# untitled.net
KiCad netlist of a schematic drawn in EAGLE
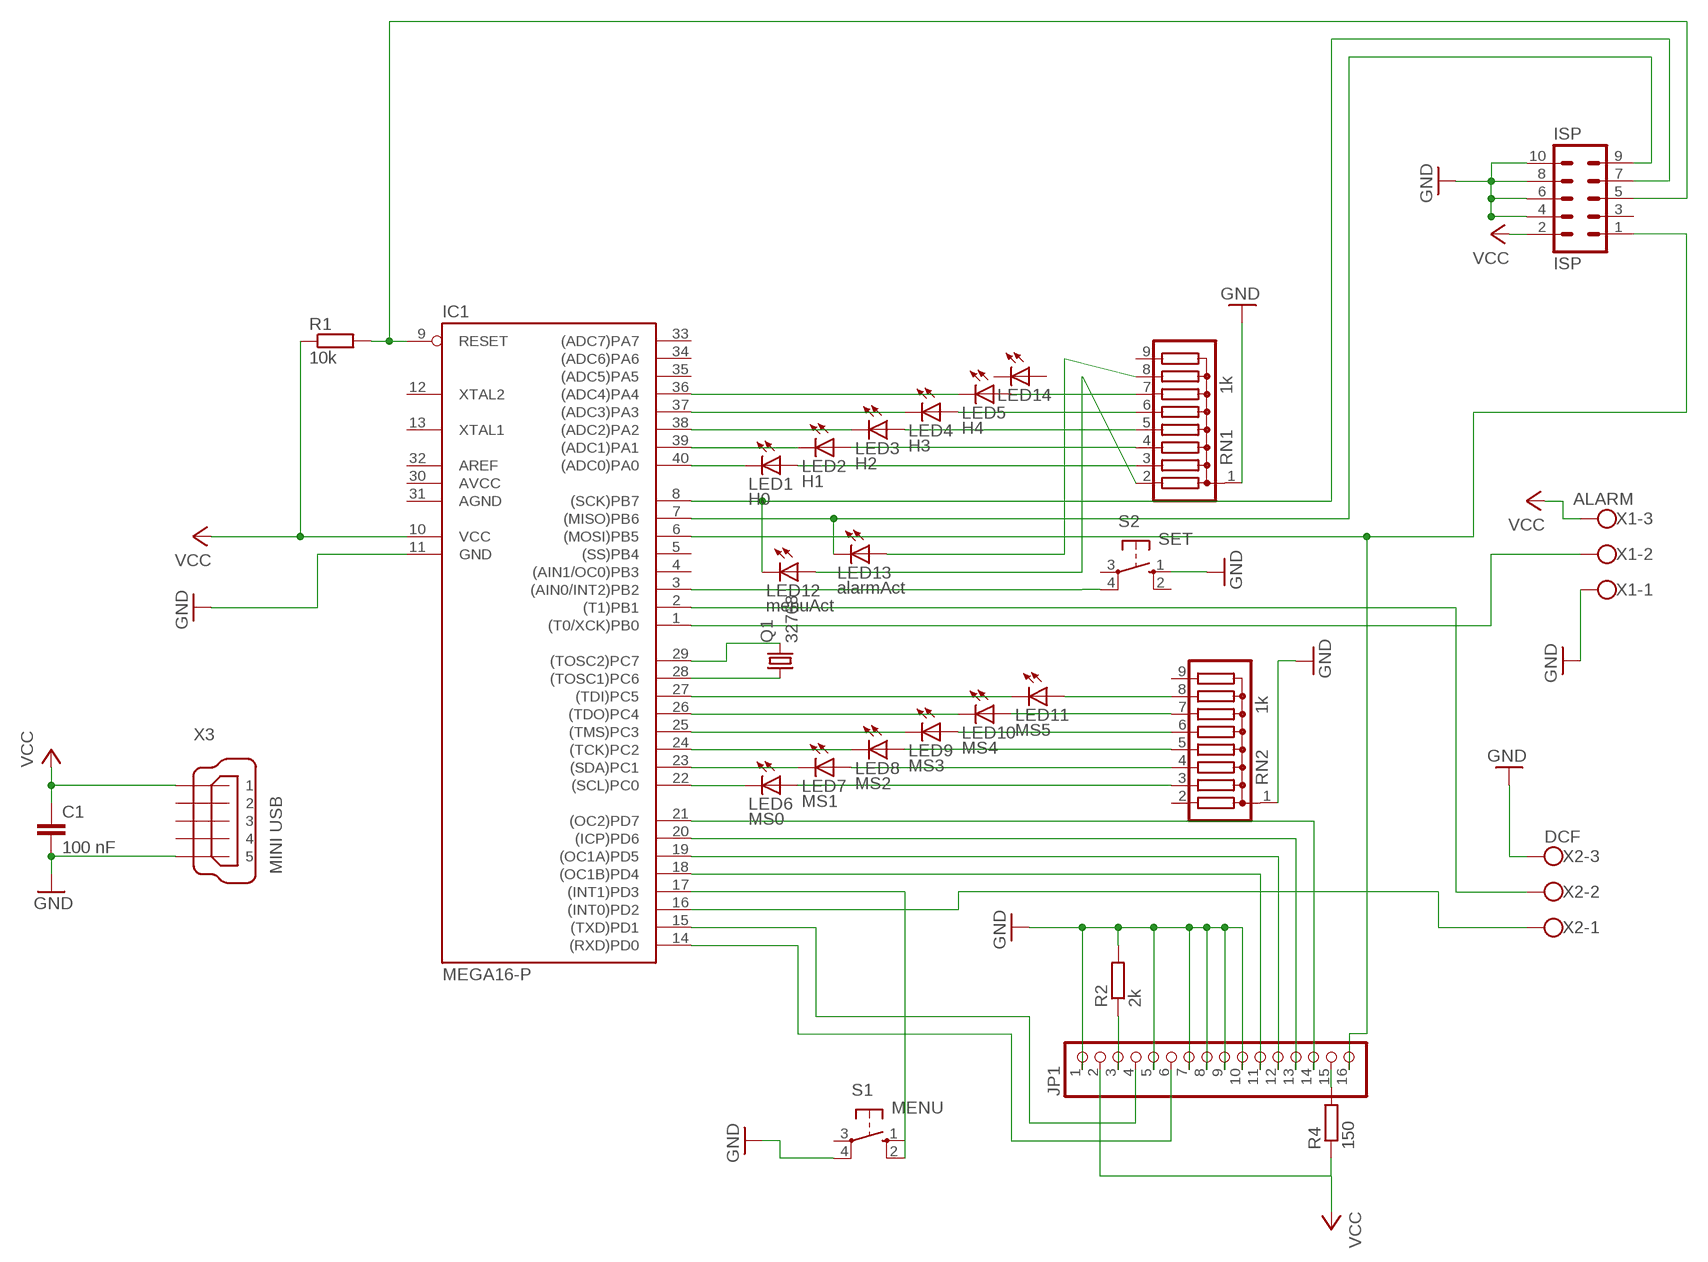
[diagram p0: schematic, sheet 1]

(export (version "E")
  (design (tool "Eeschema 10.0.6"))
  (components
    (comp (ref "C1")
      (value "100 nF")
      (footprint "eagle-import:C050-025X075")
      (libsource (lib "eagle-import") (part "C-EU050-025X075"))
    )
    (comp (ref "IC1")
      (value "MEGA16-P")
      (footprint "eagle-import:DIL40")
      (libsource (lib "eagle-import") (part "MEGA16-P"))
    )
    (comp (ref "ISP")
      (value "ISP")
      (footprint "eagle-import:ML10")
      (libsource (lib "eagle-import") (part "ML10"))
    )
    (comp (ref "JP1")
      (value "PINHD-1X16")
      (footprint "eagle-import:1X16")
      (libsource (lib "eagle-import") (part "PINHD-1X16"))
    )
    (comp (ref "LED1")
      (value "H0")
      (footprint "eagle-import:LED3MM")
      (libsource (lib "eagle-import") (part "LED3MM"))
    )
    (comp (ref "LED2")
      (value "H1")
      (footprint "eagle-import:LED3MM")
      (libsource (lib "eagle-import") (part "LED3MM"))
    )
    (comp (ref "LED3")
      (value "H2")
      (footprint "eagle-import:LED3MM")
      (libsource (lib "eagle-import") (part "LED3MM"))
    )
    (comp (ref "LED4")
      (value "H3")
      (footprint "eagle-import:LED3MM")
      (libsource (lib "eagle-import") (part "LED3MM"))
    )
    (comp (ref "LED5")
      (value "H4")
      (footprint "eagle-import:LED3MM")
      (libsource (lib "eagle-import") (part "LED3MM"))
    )
    (comp (ref "LED6")
      (value "MS0")
      (footprint "eagle-import:LED3MM")
      (libsource (lib "eagle-import") (part "LED3MM"))
    )
    (comp (ref "LED7")
      (value "MS1")
      (footprint "eagle-import:LED3MM")
      (libsource (lib "eagle-import") (part "LED3MM"))
    )
    (comp (ref "LED8")
      (value "MS2")
      (footprint "eagle-import:LED3MM")
      (libsource (lib "eagle-import") (part "LED3MM"))
    )
    (comp (ref "LED9")
      (value "MS3")
      (footprint "eagle-import:LED3MM")
      (libsource (lib "eagle-import") (part "LED3MM"))
    )
    (comp (ref "LED10")
      (value "MS4")
      (footprint "eagle-import:LED3MM")
      (libsource (lib "eagle-import") (part "LED3MM"))
    )
    (comp (ref "LED11")
      (value "MS5")
      (footprint "eagle-import:LED3MM")
      (libsource (lib "eagle-import") (part "LED3MM"))
    )
    (comp (ref "LED12")
      (value "menuAct")
      (footprint "eagle-import:LED3MM")
      (libsource (lib "eagle-import") (part "LED3MM"))
    )
    (comp (ref "LED13")
      (value "alarmAct")
      (footprint "eagle-import:LED3MM")
      (libsource (lib "eagle-import") (part "LED3MM"))
    )
    (comp (ref "LED14")
      (value "LED3MM")
      (footprint "eagle-import:LED3MM")
      (libsource (lib "eagle-import") (part "LED3MM"))
    )
    (comp (ref "Q1")
      (value "32768")
      (footprint "eagle-import:TC26V")
      (libsource (lib "eagle-import") (part "CRYSTALTC26V"))
    )
    (comp (ref "R1")
      (value "10k")
      (footprint "eagle-import:0207_10")
      (libsource (lib "eagle-import") (part "R-EU_0207/10"))
    )
    (comp (ref "R2")
      (value "2k")
      (footprint "eagle-import:0207_10")
      (libsource (lib "eagle-import") (part "R-EU_0207/10"))
    )
    (comp (ref "R4")
      (value "150")
      (footprint "eagle-import:0204_7")
      (libsource (lib "eagle-import") (part "R-EU_0204/7"))
    )
    (comp (ref "RN1")
      (value "1k")
      (footprint "eagle-import:SIL9")
      (libsource (lib "eagle-import") (part "G08R"))
    )
    (comp (ref "RN2")
      (value "1k")
      (footprint "eagle-import:SIL9")
      (libsource (lib "eagle-import") (part "G08R"))
    )
    (comp (ref "S1")
      (value "MENU")
      (footprint "eagle-import:B3F-10XX")
      (libsource (lib "eagle-import") (part "10-XX"))
    )
    (comp (ref "S2")
      (value "SET")
      (footprint "eagle-import:B3F-10XX")
      (libsource (lib "eagle-import") (part "10-XX"))
    )
    (comp (ref "X1")
      (value "ALARM")
      (footprint "eagle-import:W237-133")
      (libsource (lib "eagle-import") (part "W237-03P"))
    )
    (comp (ref "X2")
      (value "DCF")
      (footprint "eagle-import:W237-133")
      (libsource (lib "eagle-import") (part "W237-03P"))
    )
    (comp (ref "X3")
      (value "MINI USB")
      (footprint "eagle-import:32005-601")
      (libsource (lib "eagle-import") (part "MINI-USB_SHIELD5P2-32005-601"))
    )
  )
  (nets
    (net (code "1") (name "/AGND") (class "Default")
      (node (ref "IC1") (pin "31") (pinfunction "AGND_31") (pintype "power_in"))
    )
    (net (code "2") (name "/AVCC") (class "Default")
      (node (ref "IC1") (pin "30") (pinfunction "AVCC_30") (pintype "power_in"))
    )
    (net (code "3") (name "GND") (class "Default")
      (node (ref "C1") (pin "2") (pinfunction "2_2") (pintype "passive"))
      (node (ref "IC1") (pin "11") (pinfunction "GND_11") (pintype "power_in"))
      (node (ref "ISP") (pin "10") (pinfunction "10_10") (pintype "passive"))
      (node (ref "ISP") (pin "4") (pinfunction "4_4") (pintype "passive"))
      (node (ref "ISP") (pin "6") (pinfunction "6_6") (pintype "passive"))
      (node (ref "ISP") (pin "8") (pinfunction "8_8") (pintype "passive"))
      (node (ref "JP1") (pin "1") (pinfunction "1_1") (pintype "passive"))
      (node (ref "JP1") (pin "10") (pinfunction "10_10") (pintype "passive"))
      (node (ref "JP1") (pin "5") (pinfunction "5_5") (pintype "passive"))
      (node (ref "JP1") (pin "7") (pinfunction "7_7") (pintype "passive"))
      (node (ref "JP1") (pin "8") (pinfunction "8_8") (pintype "passive"))
      (node (ref "JP1") (pin "9") (pinfunction "9_9") (pintype "passive"))
      (node (ref "R2") (pin "2") (pinfunction "2_2") (pintype "passive"))
      (node (ref "RN1") (pin "1") (pinfunction "1_1") (pintype "passive"))
      (node (ref "RN2") (pin "1") (pinfunction "1_1") (pintype "passive"))
      (node (ref "S1") (pin "4") (pinfunction "P1_4") (pintype "passive"))
      (node (ref "S2") (pin "1") (pinfunction "S_1") (pintype "passive"))
      (node (ref "X1") (pin "1") (pinfunction "KL_1") (pintype "passive"))
      (node (ref "X2") (pin "3") (pinfunction "KL_3") (pintype "passive"))
      (node (ref "X3") (pin "5") (pinfunction "5_5") (pintype "passive"))
    )
    (net (code "4") (name "Net-(IC1-(ADC0)PA0)") (class "Default")
      (node (ref "IC1") (pin "40") (pinfunction "(ADC0)PA0_40") (pintype "bidirectional"))
      (node (ref "LED1") (pin "K") (pinfunction "C_K") (pintype "passive"))
    )
    (net (code "5") (name "Net-(IC1-(ADC1)PA1)") (class "Default")
      (node (ref "IC1") (pin "39") (pinfunction "(ADC1)PA1_39") (pintype "bidirectional"))
      (node (ref "LED2") (pin "K") (pinfunction "C_K") (pintype "passive"))
    )
    (net (code "6") (name "Net-(IC1-(ADC2)PA2)") (class "Default")
      (node (ref "IC1") (pin "38") (pinfunction "(ADC2)PA2_38") (pintype "bidirectional"))
      (node (ref "LED3") (pin "K") (pinfunction "C_K") (pintype "passive"))
    )
    (net (code "7") (name "Net-(IC1-(ADC3)PA3)") (class "Default")
      (node (ref "IC1") (pin "37") (pinfunction "(ADC3)PA3_37") (pintype "bidirectional"))
      (node (ref "LED4") (pin "K") (pinfunction "C_K") (pintype "passive"))
    )
    (net (code "8") (name "Net-(IC1-(ADC4)PA4)") (class "Default")
      (node (ref "IC1") (pin "36") (pinfunction "(ADC4)PA4_36") (pintype "bidirectional"))
      (node (ref "LED5") (pin "K") (pinfunction "C_K") (pintype "passive"))
    )
    (net (code "9") (name "Net-(IC1-(AIN0{slash}INT2)PB2)") (class "Default")
      (node (ref "IC1") (pin "3") (pinfunction "(AIN0/INT2)PB2_3") (pintype "bidirectional"))
      (node (ref "S2") (pin "4") (pinfunction "P1_4") (pintype "passive"))
    )
    (net (code "10") (name "Net-(IC1-(ICP)PD6)") (class "Default")
      (node (ref "IC1") (pin "20") (pinfunction "(ICP)PD6_20") (pintype "bidirectional"))
      (node (ref "JP1") (pin "13") (pinfunction "13_13") (pintype "passive"))
    )
    (net (code "11") (name "Net-(IC1-(INT0)PD2)") (class "Default")
      (node (ref "IC1") (pin "16") (pinfunction "(INT0)PD2_16") (pintype "bidirectional"))
      (node (ref "X2") (pin "1") (pinfunction "KL_1") (pintype "passive"))
    )
    (net (code "12") (name "Net-(IC1-(INT1)PD3)") (class "Default")
      (node (ref "IC1") (pin "17") (pinfunction "(INT1)PD3_17") (pintype "bidirectional"))
      (node (ref "S1") (pin "2") (pinfunction "S1_2") (pintype "passive"))
    )
    (net (code "13") (name "Net-(IC1-(MISO)PB6)") (class "Default")
      (node (ref "IC1") (pin "7") (pinfunction "(MISO)PB6_7") (pintype "bidirectional"))
      (node (ref "ISP") (pin "9") (pinfunction "9_9") (pintype "passive"))
      (node (ref "LED13") (pin "K") (pinfunction "C_K") (pintype "passive"))
    )
    (net (code "14") (name "Net-(IC1-(MOSI)PB5)") (class "Default")
      (node (ref "IC1") (pin "6") (pinfunction "(MOSI)PB5_6") (pintype "bidirectional"))
      (node (ref "ISP") (pin "1") (pinfunction "1_1") (pintype "passive"))
      (node (ref "JP1") (pin "16") (pinfunction "16_16") (pintype "passive"))
    )
    (net (code "15") (name "Net-(IC1-(OC1A)PD5)") (class "Default")
      (node (ref "IC1") (pin "19") (pinfunction "(OC1A)PD5_19") (pintype "bidirectional"))
      (node (ref "JP1") (pin "12") (pinfunction "12_12") (pintype "passive"))
    )
    (net (code "16") (name "Net-(IC1-(OC1B)PD4)") (class "Default")
      (node (ref "IC1") (pin "18") (pinfunction "(OC1B)PD4_18") (pintype "bidirectional"))
      (node (ref "JP1") (pin "11") (pinfunction "11_11") (pintype "passive"))
    )
    (net (code "17") (name "Net-(IC1-(OC2)PD7)") (class "Default")
      (node (ref "IC1") (pin "21") (pinfunction "(OC2)PD7_21") (pintype "bidirectional"))
      (node (ref "JP1") (pin "14") (pinfunction "14_14") (pintype "passive"))
    )
    (net (code "18") (name "Net-(IC1-(RXD)PD0)") (class "Default")
      (node (ref "IC1") (pin "14") (pinfunction "(RXD)PD0_14") (pintype "bidirectional"))
      (node (ref "JP1") (pin "6") (pinfunction "6_6") (pintype "passive"))
    )
    (net (code "19") (name "Net-(IC1-(SCK)PB7)") (class "Default")
      (node (ref "IC1") (pin "8") (pinfunction "(SCK)PB7_8") (pintype "bidirectional"))
      (node (ref "ISP") (pin "7") (pinfunction "7_7") (pintype "passive"))
      (node (ref "LED12") (pin "K") (pinfunction "C_K") (pintype "passive"))
    )
    (net (code "20") (name "Net-(IC1-(SCL)PC0)") (class "Default")
      (node (ref "IC1") (pin "22") (pinfunction "(SCL)PC0_22") (pintype "bidirectional"))
      (node (ref "LED6") (pin "K") (pinfunction "C_K") (pintype "passive"))
    )
    (net (code "21") (name "Net-(IC1-(SDA)PC1)") (class "Default")
      (node (ref "IC1") (pin "23") (pinfunction "(SDA)PC1_23") (pintype "bidirectional"))
      (node (ref "LED7") (pin "K") (pinfunction "C_K") (pintype "passive"))
    )
    (net (code "22") (name "Net-(IC1-(T0{slash}XCK)PB0)") (class "Default")
      (node (ref "IC1") (pin "1") (pinfunction "(T0/XCK)PB0_1") (pintype "bidirectional"))
      (node (ref "X1") (pin "2") (pinfunction "KL_2") (pintype "passive"))
    )
    (net (code "23") (name "Net-(IC1-(T1)PB1)") (class "Default")
      (node (ref "IC1") (pin "2") (pinfunction "(T1)PB1_2") (pintype "bidirectional"))
      (node (ref "X2") (pin "2") (pinfunction "KL_2") (pintype "passive"))
    )
    (net (code "24") (name "Net-(IC1-(TCK)PC2)") (class "Default")
      (node (ref "IC1") (pin "24") (pinfunction "(TCK)PC2_24") (pintype "bidirectional"))
      (node (ref "LED8") (pin "K") (pinfunction "C_K") (pintype "passive"))
    )
    (net (code "25") (name "Net-(IC1-(TDI)PC5)") (class "Default")
      (node (ref "IC1") (pin "27") (pinfunction "(TDI)PC5_27") (pintype "bidirectional"))
      (node (ref "LED11") (pin "K") (pinfunction "C_K") (pintype "passive"))
    )
    (net (code "26") (name "Net-(IC1-(TDO)PC4)") (class "Default")
      (node (ref "IC1") (pin "26") (pinfunction "(TDO)PC4_26") (pintype "bidirectional"))
      (node (ref "LED10") (pin "K") (pinfunction "C_K") (pintype "passive"))
    )
    (net (code "27") (name "Net-(IC1-(TMS)PC3)") (class "Default")
      (node (ref "IC1") (pin "25") (pinfunction "(TMS)PC3_25") (pintype "bidirectional"))
      (node (ref "LED9") (pin "K") (pinfunction "C_K") (pintype "passive"))
    )
    (net (code "28") (name "Net-(IC1-(TOSC1)PC6)") (class "Default")
      (node (ref "IC1") (pin "28") (pinfunction "(TOSC1)PC6_28") (pintype "bidirectional"))
      (node (ref "Q1") (pin "1") (pinfunction "1_1") (pintype "passive"))
    )
    (net (code "29") (name "Net-(IC1-(TOSC2)PC7)") (class "Default")
      (node (ref "IC1") (pin "29") (pinfunction "(TOSC2)PC7_29") (pintype "bidirectional"))
      (node (ref "Q1") (pin "2") (pinfunction "2_2") (pintype "passive"))
    )
    (net (code "30") (name "Net-(IC1-(TXD)PD1)") (class "Default")
      (node (ref "IC1") (pin "15") (pinfunction "(TXD)PD1_15") (pintype "bidirectional"))
      (node (ref "JP1") (pin "4") (pinfunction "4_4") (pintype "passive"))
    )
    (net (code "31") (name "Net-(IC1-RESET)") (class "Default")
      (node (ref "IC1") (pin "9") (pinfunction "RESET_9") (pintype "input"))
      (node (ref "ISP") (pin "5") (pinfunction "5_5") (pintype "passive"))
      (node (ref "R1") (pin "2") (pinfunction "2_2") (pintype "passive"))
    )
    (net (code "32") (name "Net-(JP1-Pad3)") (class "Default")
      (node (ref "JP1") (pin "3") (pinfunction "3_3") (pintype "passive"))
      (node (ref "R2") (pin "1") (pinfunction "1_1") (pintype "passive"))
    )
    (net (code "33") (name "Net-(JP1-Pad15)") (class "Default")
      (node (ref "JP1") (pin "15") (pinfunction "15_15") (pintype "passive"))
      (node (ref "R4") (pin "2") (pinfunction "2_2") (pintype "passive"))
    )
    (net (code "34") (name "Net-(LED1-PadA)") (class "Default")
      (node (ref "LED1") (pin "A") (pinfunction "A_A") (pintype "passive"))
      (node (ref "RN1") (pin "3") (pinfunction "3_3") (pintype "passive"))
    )
    (net (code "35") (name "Net-(LED2-PadA)") (class "Default")
      (node (ref "LED2") (pin "A") (pinfunction "A_A") (pintype "passive"))
      (node (ref "RN1") (pin "4") (pinfunction "4_4") (pintype "passive"))
    )
    (net (code "36") (name "Net-(LED3-PadA)") (class "Default")
      (node (ref "LED3") (pin "A") (pinfunction "A_A") (pintype "passive"))
      (node (ref "RN1") (pin "5") (pinfunction "5_5") (pintype "passive"))
    )
    (net (code "37") (name "Net-(LED4-PadA)") (class "Default")
      (node (ref "LED4") (pin "A") (pinfunction "A_A") (pintype "passive"))
      (node (ref "RN1") (pin "6") (pinfunction "6_6") (pintype "passive"))
    )
    (net (code "38") (name "Net-(LED5-PadA)") (class "Default")
      (node (ref "LED5") (pin "A") (pinfunction "A_A") (pintype "passive"))
      (node (ref "RN1") (pin "7") (pinfunction "7_7") (pintype "passive"))
    )
    (net (code "39") (name "Net-(LED6-PadA)") (class "Default")
      (node (ref "LED6") (pin "A") (pinfunction "A_A") (pintype "passive"))
      (node (ref "RN2") (pin "3") (pinfunction "3_3") (pintype "passive"))
    )
    (net (code "40") (name "Net-(LED7-PadA)") (class "Default")
      (node (ref "LED7") (pin "A") (pinfunction "A_A") (pintype "passive"))
      (node (ref "RN2") (pin "4") (pinfunction "4_4") (pintype "passive"))
    )
    (net (code "41") (name "Net-(LED8-PadA)") (class "Default")
      (node (ref "LED8") (pin "A") (pinfunction "A_A") (pintype "passive"))
      (node (ref "RN2") (pin "5") (pinfunction "5_5") (pintype "passive"))
    )
    (net (code "42") (name "Net-(LED9-PadA)") (class "Default")
      (node (ref "LED9") (pin "A") (pinfunction "A_A") (pintype "passive"))
      (node (ref "RN2") (pin "6") (pinfunction "6_6") (pintype "passive"))
    )
    (net (code "43") (name "Net-(LED10-PadA)") (class "Default")
      (node (ref "LED10") (pin "A") (pinfunction "A_A") (pintype "passive"))
      (node (ref "RN2") (pin "7") (pinfunction "7_7") (pintype "passive"))
    )
    (net (code "44") (name "Net-(LED11-PadA)") (class "Default")
      (node (ref "LED11") (pin "A") (pinfunction "A_A") (pintype "passive"))
      (node (ref "RN2") (pin "8") (pinfunction "8_8") (pintype "passive"))
    )
    (net (code "45") (name "Net-(LED12-PadA)") (class "Default")
      (node (ref "LED12") (pin "A") (pinfunction "A_A") (pintype "passive"))
      (node (ref "RN1") (pin "2") (pinfunction "2_2") (pintype "passive"))
    )
    (net (code "46") (name "Net-(LED13-PadA)") (class "Default")
      (node (ref "LED13") (pin "A") (pinfunction "A_A") (pintype "passive"))
      (node (ref "RN1") (pin "8") (pinfunction "8_8") (pintype "passive"))
    )
    (net (code "47") (name "VCC") (class "Default")
      (node (ref "C1") (pin "1") (pinfunction "1_1") (pintype "passive"))
      (node (ref "IC1") (pin "10") (pinfunction "VCC_10") (pintype "power_in"))
      (node (ref "ISP") (pin "2") (pinfunction "2_2") (pintype "passive"))
      (node (ref "JP1") (pin "2") (pinfunction "2_2") (pintype "passive"))
      (node (ref "R1") (pin "1") (pinfunction "1_1") (pintype "passive"))
      (node (ref "R4") (pin "1") (pinfunction "1_1") (pintype "passive"))
      (node (ref "X1") (pin "3") (pinfunction "KL_3") (pintype "passive"))
      (node (ref "X3") (pin "1") (pinfunction "1_1") (pintype "passive"))
    )
    (net (code "48") (name "unconnected-(IC1-(ADC5)PA5-Pad35)") (class "Default")
      (node (ref "IC1") (pin "35") (pinfunction "(ADC5)PA5_35") (pintype "bidirectional"))
    )
    (net (code "49") (name "unconnected-(IC1-(ADC6)PA6-Pad34)") (class "Default")
      (node (ref "IC1") (pin "34") (pinfunction "(ADC6)PA6_34") (pintype "bidirectional"))
    )
    (net (code "50") (name "unconnected-(IC1-(ADC7)PA7-Pad33)") (class "Default")
      (node (ref "IC1") (pin "33") (pinfunction "(ADC7)PA7_33") (pintype "bidirectional"))
    )
    (net (code "51") (name "unconnected-(IC1-(AIN1{slash}OC0)PB3-Pad4)") (class "Default")
      (node (ref "IC1") (pin "4") (pinfunction "(AIN1/OC0)PB3_4") (pintype "bidirectional"))
    )
    (net (code "52") (name "unconnected-(IC1-(SS)PB4-Pad5)") (class "Default")
      (node (ref "IC1") (pin "5") (pinfunction "(SS)PB4_5") (pintype "bidirectional"))
    )
    (net (code "53") (name "unconnected-(IC1-AREF-Pad32)") (class "Default")
      (node (ref "IC1") (pin "32") (pinfunction "AREF_32") (pintype "passive"))
    )
    (net (code "54") (name "unconnected-(IC1-XTAL1-Pad13)") (class "Default")
      (node (ref "IC1") (pin "13") (pinfunction "XTAL1_13") (pintype "bidirectional"))
    )
    (net (code "55") (name "unconnected-(IC1-XTAL2-Pad12)") (class "Default")
      (node (ref "IC1") (pin "12") (pinfunction "XTAL2_12") (pintype "bidirectional"))
    )
    (net (code "56") (name "unconnected-(ISP-Pad3)") (class "Default")
      (node (ref "ISP") (pin "3") (pinfunction "3_3") (pintype "passive"))
    )
    (net (code "57") (name "unconnected-(LED14-C-PadK)") (class "Default")
      (node (ref "LED14") (pin "K") (pinfunction "C_K") (pintype "passive"))
    )
    (net (code "58") (name "unconnected-(LED14-PadA)") (class "Default")
      (node (ref "LED14") (pin "A") (pinfunction "A_A") (pintype "passive"))
    )
    (net (code "59") (name "unconnected-(RN1-Pad9)") (class "Default")
      (node (ref "RN1") (pin "9") (pinfunction "9_9") (pintype "passive"))
    )
    (net (code "60") (name "unconnected-(RN2-Pad2)") (class "Default")
      (node (ref "RN2") (pin "2") (pinfunction "2_2") (pintype "passive"))
    )
    (net (code "61") (name "unconnected-(RN2-Pad9)") (class "Default")
      (node (ref "RN2") (pin "9") (pinfunction "9_9") (pintype "passive"))
    )
    (net (code "62") (name "unconnected-(S1-P-Pad3)") (class "Default")
      (node (ref "S1") (pin "3") (pinfunction "P_3") (pintype "passive"))
    )
    (net (code "63") (name "unconnected-(S1-S-Pad1)") (class "Default")
      (node (ref "S1") (pin "1") (pinfunction "S_1") (pintype "passive"))
    )
    (net (code "64") (name "unconnected-(S2-P-Pad3)") (class "Default")
      (node (ref "S2") (pin "3") (pinfunction "P_3") (pintype "passive"))
    )
    (net (code "65") (name "unconnected-(S2-S1-Pad2)") (class "Default")
      (node (ref "S2") (pin "2") (pinfunction "S1_2") (pintype "passive"))
    )
    (net (code "66") (name "unconnected-(X3-Pad2)") (class "Default")
      (node (ref "X3") (pin "2") (pinfunction "2_2") (pintype "passive"))
    )
    (net (code "67") (name "unconnected-(X3-Pad3)") (class "Default")
      (node (ref "X3") (pin "3") (pinfunction "3_3") (pintype "passive"))
    )
    (net (code "68") (name "unconnected-(X3-Pad4)") (class "Default")
      (node (ref "X3") (pin "4") (pinfunction "4_4") (pintype "passive"))
    )
  )
)
